# New_Project_2024-09-21_02-08-15.net
KiCad netlist of a schematic drawn in EasyEDA Pro
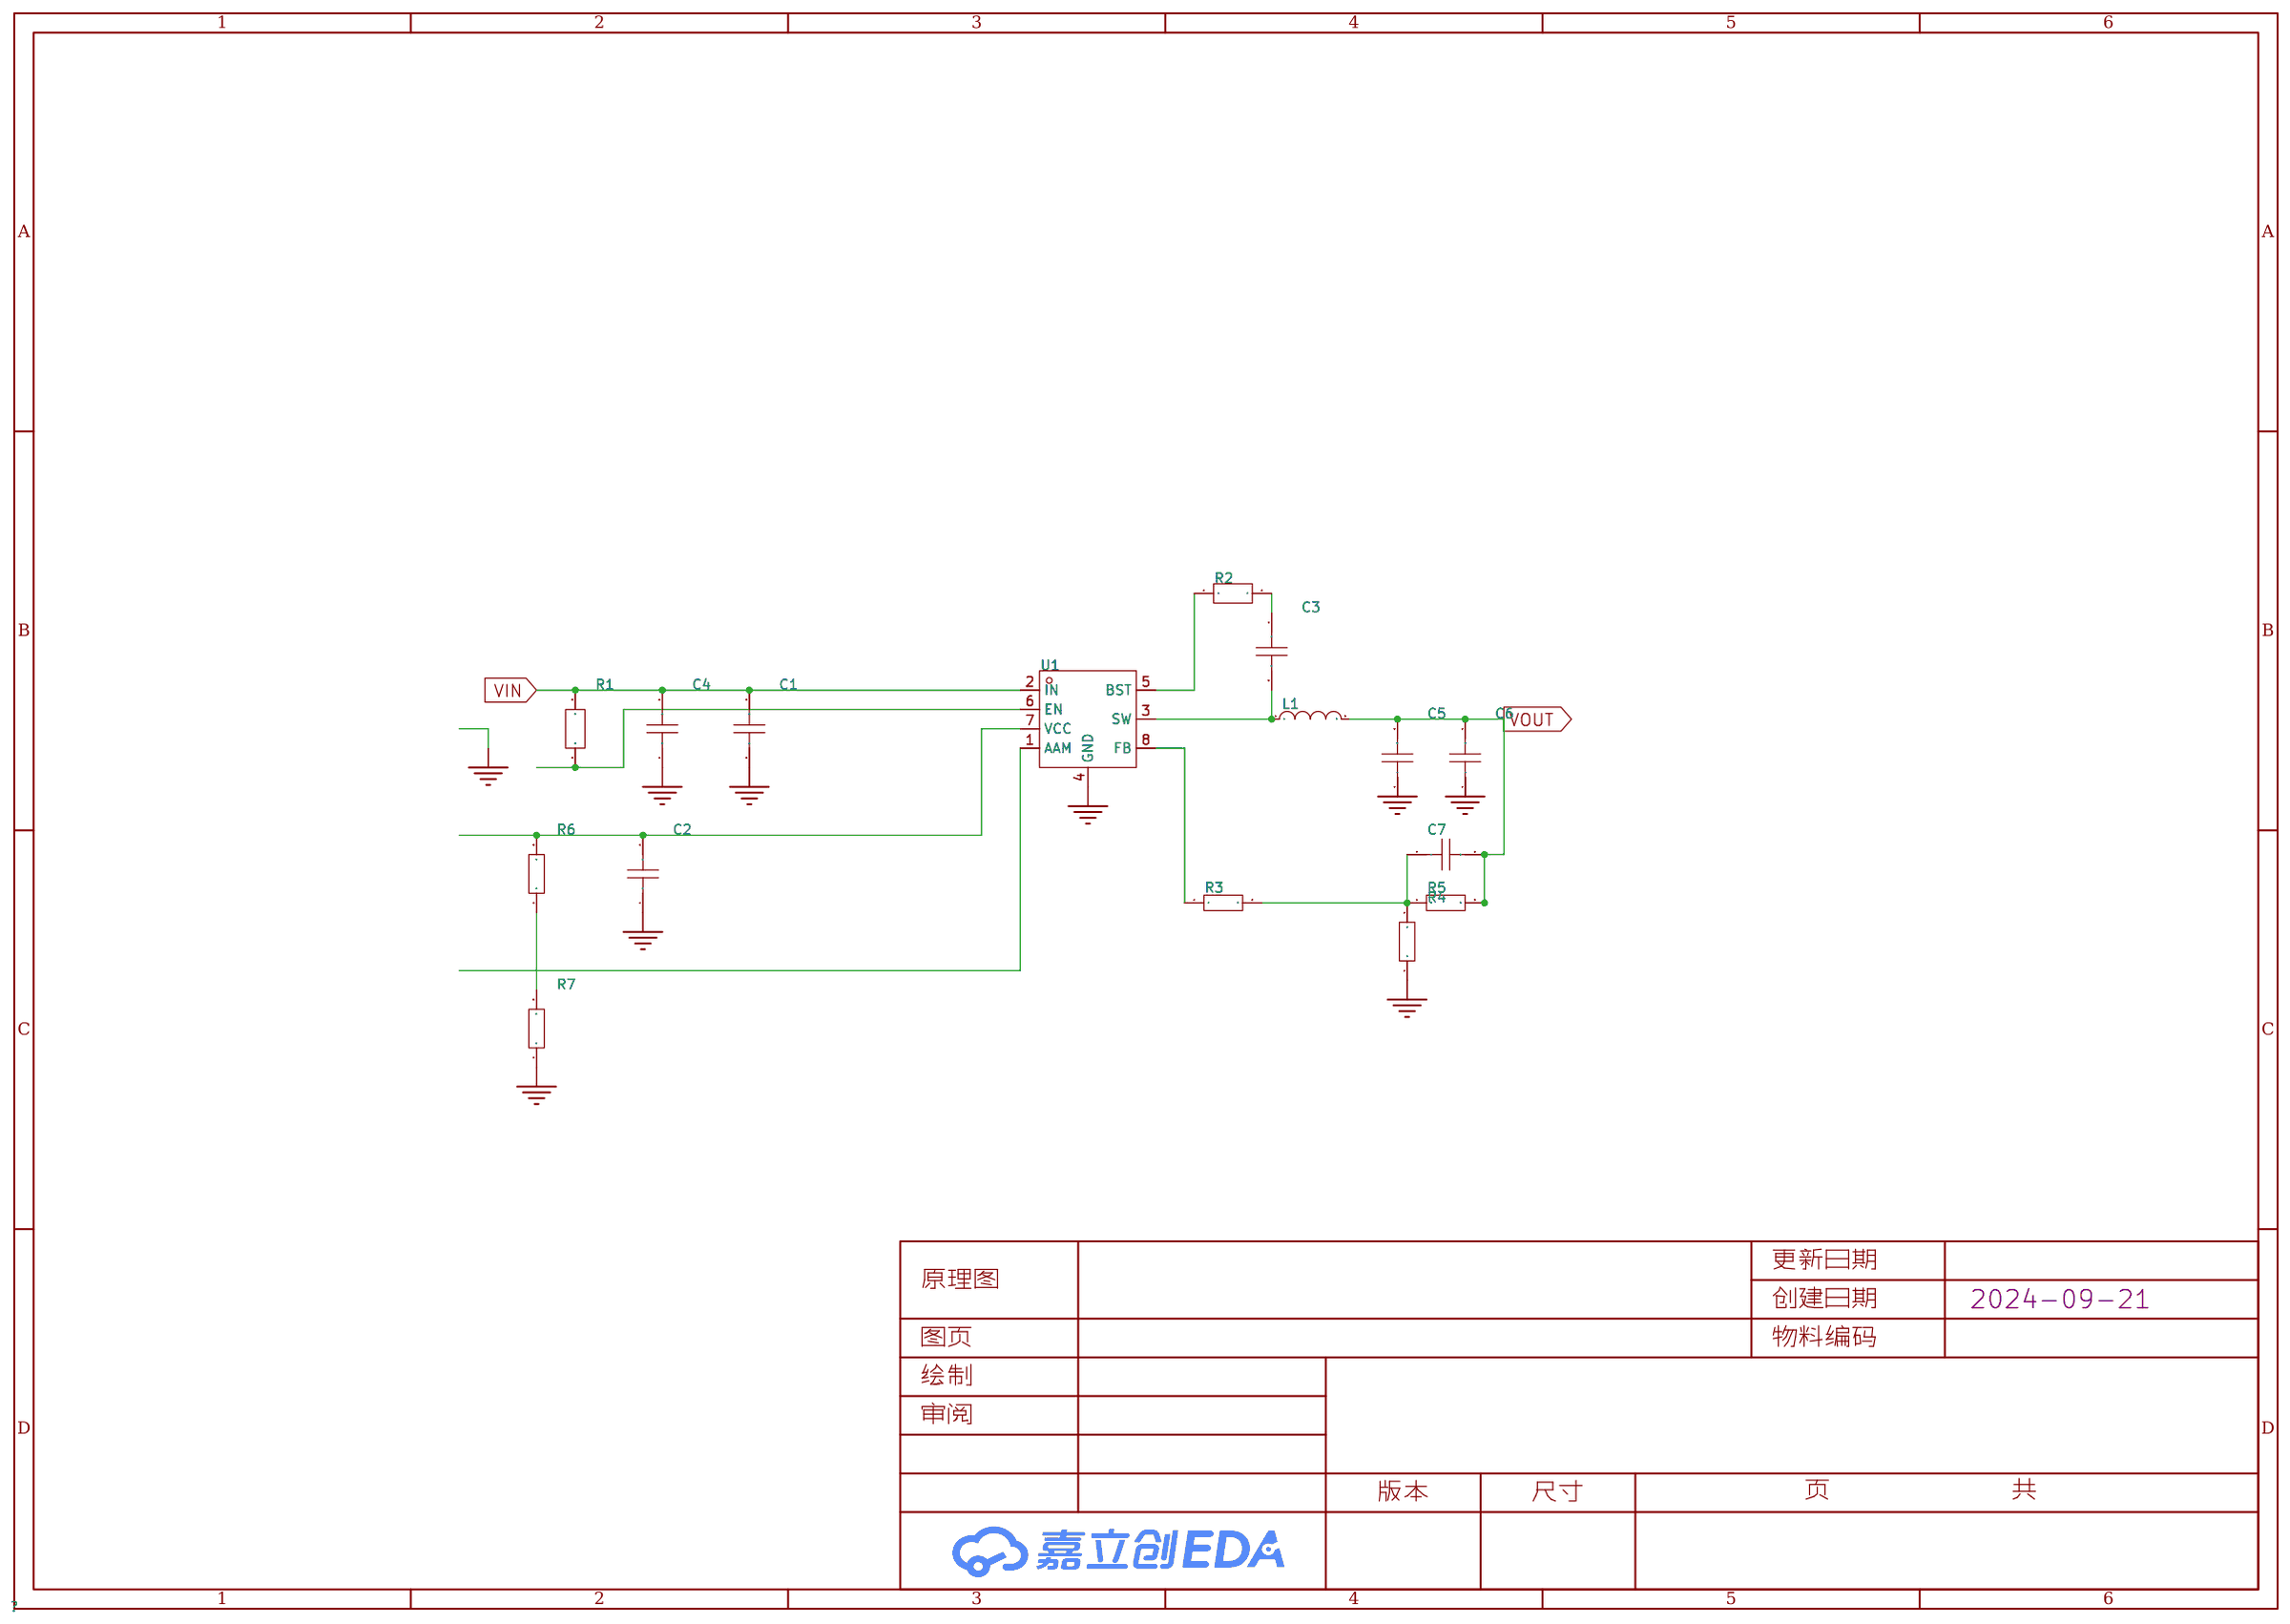
[diagram p0: schematic sheet]

(export (version "E")
  (design (tool "Eeschema 10.0.6"))
  (components
    (comp (ref "C1")
      (value "100nF")
      (footprint "easyedapro:C0603")
      (description "容值:100nF;精度:±10%;额定电压:50V;材质(温度系数):X7R;")
      (fields
        (field (name "Manufacturer Part") "CGA0603X7R104K500JT")
        (field (name "Manufacturer") "HRE(芯声)")
      )
      (libsource (lib "easyedapro") (part "CGA0603X7R104K500JT"))
    )
    (comp (ref "C2")
      (value "100nF")
      (footprint "easyedapro:C0603")
      (description "容值:100nF;精度:±10%;额定电压:50V;材质(温度系数):X7R;")
      (fields
        (field (name "Manufacturer Part") "CGA0603X7R104K500JT")
        (field (name "Manufacturer") "HRE(芯声)")
      )
      (libsource (lib "easyedapro") (part "CGA0603X7R104K500JT"))
    )
    (comp (ref "C3")
      (value "100nF")
      (footprint "easyedapro:C0603")
      (description "容值:100nF;精度:±10%;额定电压:50V;材质(温度系数):X7R;")
      (fields
        (field (name "Manufacturer Part") "CGA0603X7R104K500JT")
        (field (name "Manufacturer") "HRE(芯声)")
      )
      (libsource (lib "easyedapro") (part "CGA0603X7R104K500JT"))
    )
    (comp (ref "C4")
      (value "22uF")
      (footprint "easyedapro:C0805")
      (description "容值:22uF;精度:±20%;额定电压:35V;材质(温度系数):X5R;")
      (fields
        (field (name "Manufacturer Part") "CGA0805X5R226M350MT")
        (field (name "Manufacturer") "HRE(芯声)")
      )
      (libsource (lib "easyedapro") (part "CGA0805X5R226M350MT"))
    )
    (comp (ref "C5")
      (value "22uF")
      (footprint "easyedapro:C0805")
      (description "容值:22uF;精度:±20%;额定电压:35V;材质(温度系数):X5R;")
      (fields
        (field (name "Manufacturer Part") "CGA0805X5R226M350MT")
        (field (name "Manufacturer") "HRE(芯声)")
      )
      (libsource (lib "easyedapro") (part "CGA0805X5R226M350MT"))
    )
    (comp (ref "C6")
      (value "22uF")
      (footprint "easyedapro:C0805")
      (description "容值:22uF;精度:±20%;额定电压:35V;材质(温度系数):X5R;")
      (fields
        (field (name "Manufacturer Part") "CGA0805X5R226M350MT")
        (field (name "Manufacturer") "HRE(芯声)")
      )
      (libsource (lib "easyedapro") (part "CGA0805X5R226M350MT"))
    )
    (comp (ref "C7")
      (value "22uF")
      (footprint "easyedapro:C0805")
      (description "容值:22uF;精度:±20%;额定电压:35V;材质(温度系数):X5R;")
      (fields
        (field (name "Manufacturer Part") "CGA0805X5R226M350MT")
        (field (name "Manufacturer") "HRE(芯声)")
      )
      (libsource (lib "easyedapro") (part "CGA0805X5R226M350MT"))
    )
    (comp (ref "L1")
      (value "4.9uH")
      (footprint "easyedapro:IND-SMD_L6.9-W6.9-LS7.0")
      (description "电感值:4.9uH;精度:±20%;额定电流:6.5A;饱和电流(Isat):6.5A;直流电阻(DCR):6.5mΩ;")
      (fields (field (name "Manufacturer Part") "FHC7050-4R9M") (field (name "Manufacturer") "KOHERelec(科或)"))
      (libsource (lib "easyedapro") (part "FHC7050-4R9M"))
    )
    (comp (ref "R1")
      (value "10kΩ")
      (footprint "easyedapro:R0603")
      (description "电阻类型:厚膜电阻;阻值:10kΩ;精度:±5%;功率:100mW;最大工作电压:75V;温度系数:±100ppm/°C;")
      (fields (field (name "Manufacturer Part") "FRC0603J103TS") (field (name "Manufacturer") "FOJAN(富捷)"))
      (libsource (lib "easyedapro") (part "FRC0603J103TS"))
    )
    (comp (ref "R2")
      (value "10kΩ")
      (footprint "easyedapro:R0603")
      (description "电阻类型:厚膜电阻;阻值:10kΩ;精度:±5%;功率:100mW;最大工作电压:75V;温度系数:±100ppm/°C;")
      (fields (field (name "Manufacturer Part") "FRC0603J103TS") (field (name "Manufacturer") "FOJAN(富捷)"))
      (libsource (lib "easyedapro") (part "FRC0603J103TS"))
    )
    (comp (ref "R3")
      (value "20kΩ")
      (footprint "easyedapro:R0603")
      (description "电阻类型:厚膜电阻;阻值:20kΩ;精度:±1%;功率:100mW;最大工作电压:75V;温度系数:±100ppm/°C;")
      (fields
        (field (name "Manufacturer Part") "0603WAF2002T5E")
        (field (name "Manufacturer") "UNI-ROYAL(厚声)")
      )
      (libsource (lib "easyedapro") (part "0603WAF2002T5E"))
    )
    (comp (ref "R4")
      (value "7.5kΩ")
      (footprint "easyedapro:R0402")
      (description "电阻类型:厚膜电阻;阻值:7.5kΩ;精度:±1%;功率:62.5mW;最大工作电压:50V;温度系数:±100ppm/°C;")
      (fields
        (field (name "Manufacturer Part") "0402WGF7501TCE")
        (field (name "Manufacturer") "UNI-ROYAL(厚声)")
      )
      (libsource (lib "easyedapro") (part "0402WGF7501TCE"))
    )
    (comp (ref "R5")
      (value "40.2kΩ")
      (footprint "easyedapro:R0603")
      (description "电阻类型:厚膜电阻;阻值:40.2kΩ;精度:±1%;功率:100mW;最大工作电压:75V;温度系数:±100ppm/°C;")
      (fields
        (field (name "Manufacturer Part") "0603WAF4022T5E")
        (field (name "Manufacturer") "UNI-ROYAL(厚声)")
      )
      (libsource (lib "easyedapro") (part "0603WAF4022T5E"))
    )
    (comp (ref "R6")
      (value "100kΩ")
      (footprint "easyedapro:R0402")
      (description "电阻类型:厚膜电阻;阻值:100kΩ;精度:±1%;功率:62.5mW;最大工作电压:50V;温度系数:±100ppm/°C;")
      (fields (field (name "Manufacturer Part") "RC0402FR-07100KL") (field (name "Manufacturer") "YAGEO(国巨)"))
      (libsource (lib "easyedapro") (part "RC0402FR-07100KL"))
    )
    (comp (ref "R7")
      (value "9.09kΩ")
      (footprint "easyedapro:R0603")
      (description "电阻类型:厚膜电阻;阻值:9.09kΩ;精度:±1%;功率:100mW;最大工作电压:75V;温度系数:±100ppm/°C;")
      (fields
        (field (name "Manufacturer Part") "0603WAF9091T5E")
        (field (name "Manufacturer") "UNI-ROYAL(厚声)")
      )
      (libsource (lib "easyedapro") (part "0603WAF9091T5E"))
    )
    (comp (ref "U1")
      (value "MP2315SGJ-Z")
      (footprint "easyedapro:TSOT-23-8_L2.9-W1.6-P0.65-LS2.8-BL")
      (description "功能类型:降压型;输出类型:可调;输入电压:4.5V~24V;输出电压:800mV~22.8V;输出电流:3A;")
      (fields (field (name "Manufacturer") "MPS(芯源)"))
      (libsource (lib "easyedapro") (part "MP2315SGJ-Z"))
    )
  )
  (nets
    (net (code "1") (name "GND") (class "Default")
      (node (ref "C1") (pin "1") (pinfunction "1_1") (pintype "unspecified"))
      (node (ref "C2") (pin "1") (pinfunction "1_1") (pintype "unspecified"))
      (node (ref "C4") (pin "1") (pinfunction "1_1") (pintype "unspecified"))
      (node (ref "C5") (pin "1") (pinfunction "1_1") (pintype "unspecified"))
      (node (ref "C6") (pin "1") (pinfunction "1_1") (pintype "unspecified"))
      (node (ref "R4") (pin "1") (pinfunction "1_1") (pintype "input"))
      (node (ref "R7") (pin "1") (pinfunction "1_1") (pintype "input"))
      (node (ref "U1") (pin "4") (pinfunction "GND_4") (pintype "unspecified"))
    )
    (net (code "2") (name "Net-(C3-Pad1)") (class "Default")
      (node (ref "C3") (pin "1") (pinfunction "1_1") (pintype "unspecified"))
      (node (ref "R2") (pin "2") (pinfunction "2_2") (pintype "unspecified"))
    )
    (net (code "3") (name "Net-(C7-Pad1)") (class "Default")
      (node (ref "C7") (pin "1") (pinfunction "1_1") (pintype "unspecified"))
      (node (ref "R3") (pin "2") (pinfunction "2_2") (pintype "input"))
      (node (ref "R4") (pin "2") (pinfunction "2_2") (pintype "input"))
      (node (ref "R5") (pin "1") (pinfunction "1_1") (pintype "input"))
    )
    (net (code "4") (name "Net-(R6-Pad1)") (class "Default")
      (node (ref "R6") (pin "1") (pinfunction "1_1") (pintype "input"))
      (node (ref "R7") (pin "2") (pinfunction "2_2") (pintype "input"))
    )
    (net (code "5") (name "Net-(U1-BST)") (class "Default")
      (node (ref "R2") (pin "1") (pinfunction "1_1") (pintype "unspecified"))
      (node (ref "U1") (pin "5") (pinfunction "BST_5") (pintype "unspecified"))
    )
    (net (code "6") (name "Net-(U1-EN)") (class "Default")
      (node (ref "R1") (pin "1") (pinfunction "1_1") (pintype "unspecified"))
      (node (ref "U1") (pin "6") (pinfunction "EN_6") (pintype "unspecified"))
    )
    (net (code "7") (name "Net-(U1-FB)") (class "Default")
      (node (ref "R3") (pin "1") (pinfunction "1_1") (pintype "input"))
      (node (ref "U1") (pin "8") (pinfunction "FB_8") (pintype "unspecified"))
    )
    (net (code "8") (name "Net-(U1-SW)") (class "Default")
      (node (ref "C3") (pin "2") (pinfunction "2_2") (pintype "unspecified"))
      (node (ref "L1") (pin "1") (pinfunction "1_1") (pintype "unspecified"))
      (node (ref "U1") (pin "3") (pinfunction "SW_3") (pintype "unspecified"))
    )
    (net (code "9") (name "Net-(U1-VCC)") (class "Default")
      (node (ref "C2") (pin "2") (pinfunction "2_2") (pintype "unspecified"))
      (node (ref "R6") (pin "2") (pinfunction "2_2") (pintype "input"))
      (node (ref "U1") (pin "7") (pinfunction "VCC_7") (pintype "unspecified"))
    )
    (net (code "10") (name "VIN") (class "Default")
      (node (ref "C1") (pin "2") (pinfunction "2_2") (pintype "unspecified"))
      (node (ref "C4") (pin "2") (pinfunction "2_2") (pintype "unspecified"))
      (node (ref "R1") (pin "2") (pinfunction "2_2") (pintype "unspecified"))
      (node (ref "U1") (pin "2") (pinfunction "IN_2") (pintype "unspecified"))
    )
    (net (code "11") (name "VOUT") (class "Default")
      (node (ref "C5") (pin "2") (pinfunction "2_2") (pintype "unspecified"))
      (node (ref "C6") (pin "2") (pinfunction "2_2") (pintype "unspecified"))
      (node (ref "C7") (pin "2") (pinfunction "2_2") (pintype "unspecified"))
      (node (ref "L1") (pin "2") (pinfunction "2_2") (pintype "unspecified"))
      (node (ref "R5") (pin "2") (pinfunction "2_2") (pintype "input"))
    )
    (net (code "12") (name "unconnected-(U1-AAM-Pad1)") (class "Default")
      (node (ref "U1") (pin "1") (pinfunction "AAM_1") (pintype "unspecified"))
    )
  )
)
